# flashlight.net
KiCad netlist of a schematic drawn in EAGLE
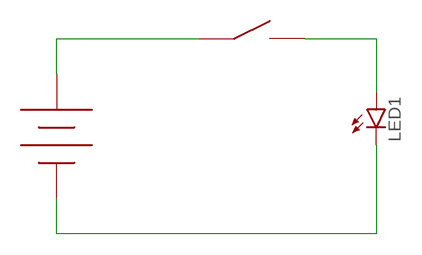
[diagram p0: schematic, sheet 1]

(export (version "E")
  (design (tool "Eeschema 10.0.6"))
  (components
    (comp (ref "LED1")
      (value "LED5MM")
      (footprint "eagle-import:LED5MM")
      (libsource (lib "eagle-import") (part "LED5MM"))
    )
    (comp (ref "U$1")
      (value "2032HOLDER")
      (footprint "eagle-import:2032HOLDER")
      (libsource (lib "eagle-import") (part "2032HOLDER"))
    )
    (comp (ref "U$2")
      (value "TACT_SWITCH")
      (footprint "eagle-import:TACT_SWITCH")
      (libsource (lib "eagle-import") (part "TACT_SWITCH"))
    )
  )
  (nets
    (net (code "1") (name "Net-(LED1-C)") (class "Default")
      (node (ref "LED1") (pin "K") (pinfunction "C_K") (pintype "passive"))
      (node (ref "U$1") (pin "NEG") (pinfunction "NEG_NEG") (pintype "bidirectional"))
    )
    (net (code "2") (name "Net-(LED1-PadA)") (class "Default")
      (node (ref "LED1") (pin "A") (pinfunction "A_A") (pintype "passive"))
      (node (ref "U$2") (pin "3") (pinfunction "3_3") (pintype "bidirectional"))
      (node (ref "U$2") (pin "4") (pinfunction "3_4") (pintype "bidirectional"))
    )
    (net (code "3") (name "Net-(U$1-PadPOS)") (class "Default")
      (node (ref "U$1") (pin "POS") (pinfunction "POS_POS") (pintype "bidirectional"))
      (node (ref "U$2") (pin "1") (pinfunction "1_1") (pintype "bidirectional"))
      (node (ref "U$2") (pin "2") (pinfunction "1_2") (pintype "bidirectional"))
    )
  )
)
